# SHEET1.net
KiCad netlist of a schematic drawn in Altium Designer
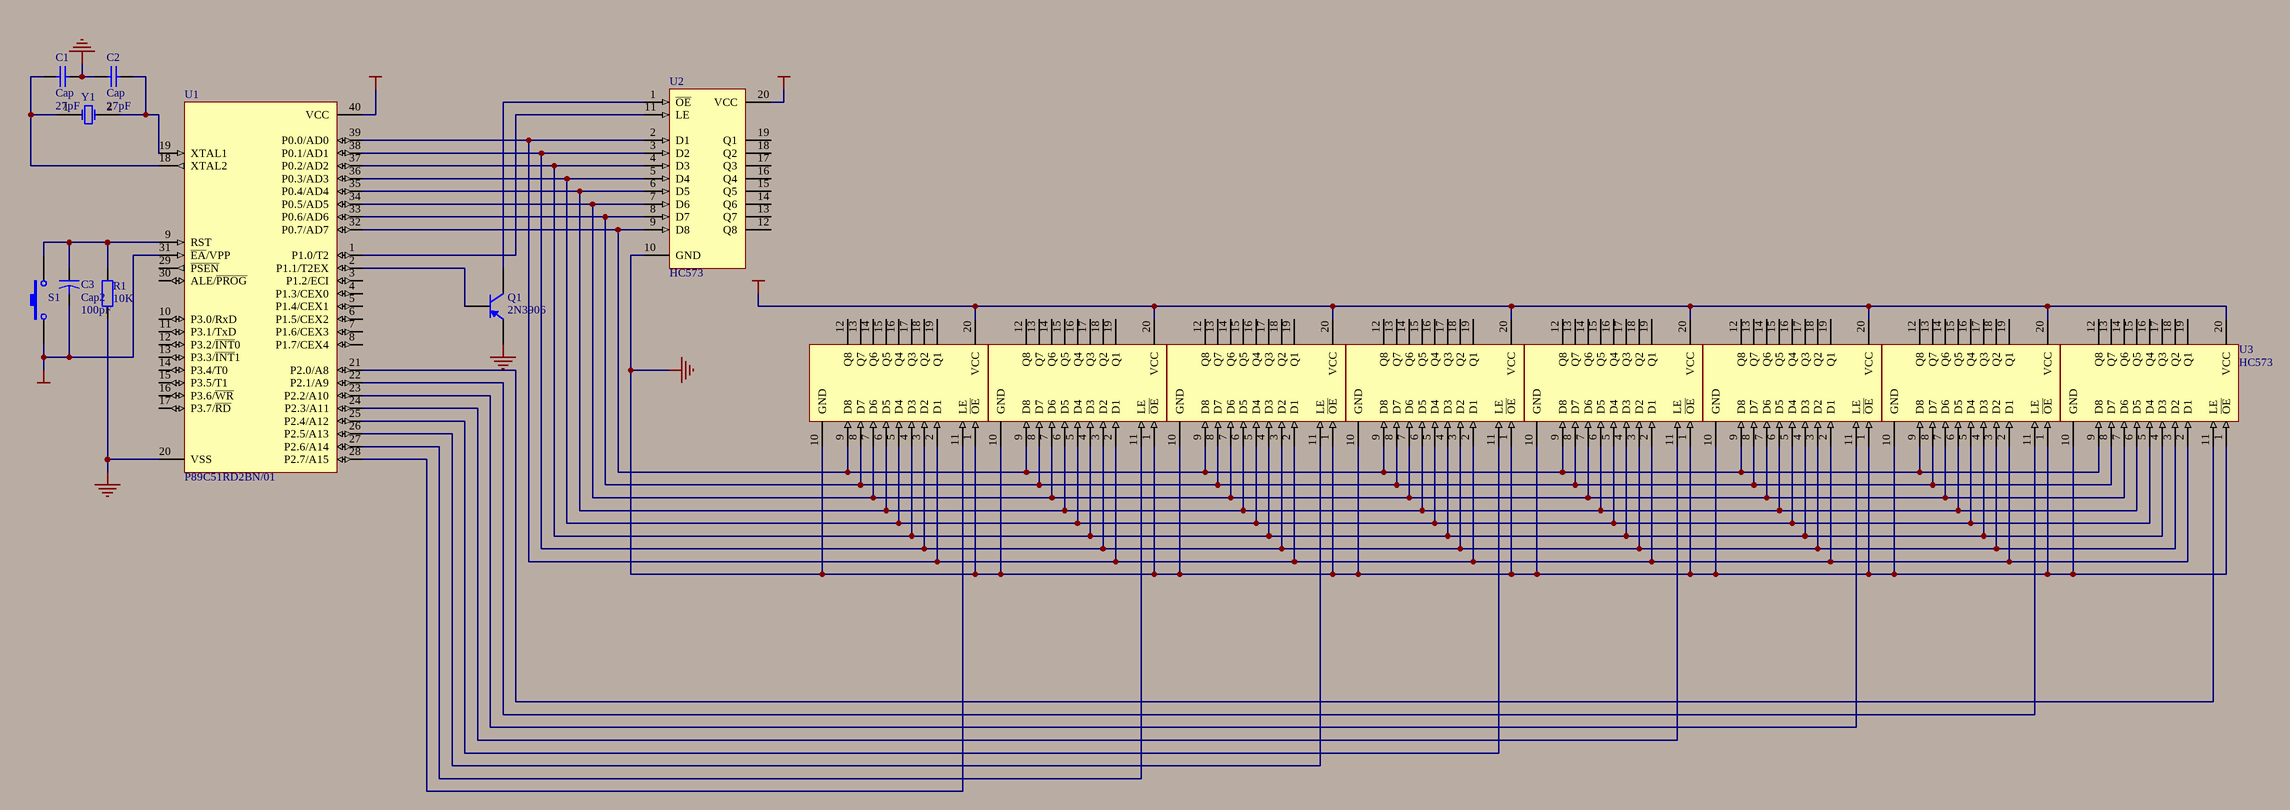
[diagram p0: SHEET1.SCHDOC]

(export (version "E")
  (design (tool "Eeschema 10.0.6"))
  (components
    (comp (ref "7")
      (value "HC573")
      (footprint "CDIP20")
      (description "Octal D-Type Latch with 3-State Output Non-Inverting")
      (fields (field (name "PUBLISHER") "Altium Limited"))
      (libsource (lib "ST Logic Latch") (part "M54HC573F1R"))
    )
    (comp (ref "C1")
      (value "Cap")
      (footprint "RAD-0.3")
      (description "Capacitor")
      (fields (field (name "ALTIUM_VALUE") "27pF") (field (name "PUBLISHER") "Altium Limited"))
      (libsource (lib "Miscellaneous Devices") (part "Cap"))
    )
    (comp (ref "C2")
      (value "Cap")
      (footprint "RAD-0.3")
      (description "Capacitor")
      (fields (field (name "ALTIUM_VALUE") "27pF") (field (name "PUBLISHER") "Altium Limited"))
      (libsource (lib "Miscellaneous Devices") (part "Cap"))
    )
    (comp (ref "C3")
      (value "Cap2")
      (footprint "CAPR5-4X5")
      (description "Capacitor")
      (fields (field (name "ALTIUM_VALUE") "100pF") (field (name "PUBLISHER") "Altium Limited"))
      (libsource (lib "Miscellaneous Devices") (part "Cap2"))
    )
    (comp (ref "Q1")
      (value "2N3906")
      (footprint "BCY-W3/E4")
      (description "PNP General Purpose Amplifier")
      (fields (field (name "PUBLISHER") "Altium Limited"))
      (libsource (lib "Miscellaneous Devices") (part "2N3906"))
    )
    (comp (ref "R1")
      (value "10K")
      (footprint "AXIAL-0.4")
      (description "Resistor")
      (fields (field (name "Comment") "Res2") (field (name "PUBLISHER") "Altium Limited"))
      (libsource (lib "Miscellaneous Devices") (part "Res2"))
    )
    (comp (ref "S1")
      (value "SW-PB")
      (footprint "SPST-2")
      (description "Switch")
      (fields (field (name "PUBLISHER") "Altium Limited"))
      (libsource (lib "Miscellaneous Devices") (part "SW-PB"))
    )
    (comp (ref "U1")
      (value "P89C51RD2BN/01")
      (footprint "SOT129-1")
      (description "80C51 8-Bit Flash Microcontroller Family, 64 kB ISP/IAP Flash with 1 kB RAM.")
      (fields (field (name "PUBLISHER") "Altium Limited"))
      (libsource (lib "Philips Microcontroller 8-Bit") (part "P89C51RD2BN/01"))
    )
    (comp (ref "U2")
      (value "HC573")
      (footprint "CDIP20")
      (description "Octal D-Type Latch with 3-State Output Non-Inverting")
      (fields (field (name "PUBLISHER") "Altium Limited"))
      (libsource (lib "ST Logic Latch") (part "M54HC573F1R"))
    )
    (comp (ref "U3")
      (value "HC573")
      (footprint "CDIP20")
      (description "Octal D-Type Latch with 3-State Output Non-Inverting")
      (fields (field (name "PUBLISHER") "Altium Limited"))
      (libsource (lib "ST Logic Latch") (part "M54HC573F1R"))
    )
    (comp (ref "U4")
      (value "HC573")
      (footprint "CDIP20")
      (description "Octal D-Type Latch with 3-State Output Non-Inverting")
      (fields (field (name "PUBLISHER") "Altium Limited"))
      (libsource (lib "ST Logic Latch") (part "M54HC573F1R"))
    )
    (comp (ref "U5")
      (value "HC573")
      (footprint "CDIP20")
      (description "Octal D-Type Latch with 3-State Output Non-Inverting")
      (fields (field (name "PUBLISHER") "Altium Limited"))
      (libsource (lib "ST Logic Latch") (part "M54HC573F1R"))
    )
    (comp (ref "U6")
      (value "HC573")
      (footprint "CDIP20")
      (description "Octal D-Type Latch with 3-State Output Non-Inverting")
      (fields (field (name "PUBLISHER") "Altium Limited"))
      (libsource (lib "ST Logic Latch") (part "M54HC573F1R"))
    )
    (comp (ref "U8")
      (value "HC573")
      (footprint "CDIP20")
      (description "Octal D-Type Latch with 3-State Output Non-Inverting")
      (fields (field (name "PUBLISHER") "Altium Limited"))
      (libsource (lib "ST Logic Latch") (part "M54HC573F1R"))
    )
    (comp (ref "U9")
      (value "HC573")
      (footprint "CDIP20")
      (description "Octal D-Type Latch with 3-State Output Non-Inverting")
      (fields (field (name "PUBLISHER") "Altium Limited"))
      (libsource (lib "ST Logic Latch") (part "M54HC573F1R"))
    )
    (comp (ref "U10")
      (value "HC573")
      (footprint "CDIP20")
      (description "Octal D-Type Latch with 3-State Output Non-Inverting")
      (fields (field (name "PUBLISHER") "Altium Limited"))
      (libsource (lib "ST Logic Latch") (part "M54HC573F1R"))
    )
    (comp (ref "Y1")
      (value "XTAL")
      (footprint "BCY-W2/D3.1")
      (description "Crystal Oscillator")
      (fields (field (name "PUBLISHER") "Altium Limited"))
      (libsource (lib "Miscellaneous Devices") (part "XTAL"))
    )
  )
  (nets
    (net (code "1") (name "GND") (class "Default")
      (node (ref "7") (pin "1") (pinfunction "~{OE}_1") (pintype "input"))
      (node (ref "7") (pin "10") (pinfunction "GND_10") (pintype "power_in"))
      (node (ref "C1") (pin "2") (pinfunction "2_2") (pintype "passive"))
      (node (ref "C2") (pin "1") (pinfunction "1_1") (pintype "passive"))
      (node (ref "Q1") (pin "1") (pinfunction "E_1") (pintype "passive"))
      (node (ref "R1") (pin "1") (pinfunction "1_1") (pintype "passive"))
      (node (ref "U1") (pin "20") (pinfunction "VSS_20") (pintype "power_in"))
      (node (ref "U10") (pin "1") (pinfunction "~{OE}_1") (pintype "input"))
      (node (ref "U10") (pin "10") (pinfunction "GND_10") (pintype "power_in"))
      (node (ref "U2") (pin "10") (pinfunction "GND_10") (pintype "power_in"))
      (node (ref "U3") (pin "1") (pinfunction "~{OE}_1") (pintype "input"))
      (node (ref "U3") (pin "10") (pinfunction "GND_10") (pintype "power_in"))
      (node (ref "U4") (pin "1") (pinfunction "~{OE}_1") (pintype "input"))
      (node (ref "U4") (pin "10") (pinfunction "GND_10") (pintype "power_in"))
      (node (ref "U5") (pin "1") (pinfunction "~{OE}_1") (pintype "input"))
      (node (ref "U5") (pin "10") (pinfunction "GND_10") (pintype "power_in"))
      (node (ref "U6") (pin "1") (pinfunction "~{OE}_1") (pintype "input"))
      (node (ref "U6") (pin "10") (pinfunction "GND_10") (pintype "power_in"))
      (node (ref "U8") (pin "1") (pinfunction "~{OE}_1") (pintype "input"))
      (node (ref "U8") (pin "10") (pinfunction "GND_10") (pintype "power_in"))
      (node (ref "U9") (pin "1") (pinfunction "~{OE}_1") (pintype "input"))
      (node (ref "U9") (pin "10") (pinfunction "GND_10") (pintype "power_in"))
    )
    (net (code "2") (name "Net-(7-D1)") (class "Default")
      (node (ref "7") (pin "2") (pinfunction "D1_2") (pintype "input"))
      (node (ref "U1") (pin "39") (pinfunction "P0.0/AD0_39") (pintype "bidirectional"))
      (node (ref "U10") (pin "2") (pinfunction "D1_2") (pintype "input"))
      (node (ref "U2") (pin "2") (pinfunction "D1_2") (pintype "input"))
      (node (ref "U3") (pin "2") (pinfunction "D1_2") (pintype "input"))
      (node (ref "U4") (pin "2") (pinfunction "D1_2") (pintype "input"))
      (node (ref "U5") (pin "2") (pinfunction "D1_2") (pintype "input"))
      (node (ref "U6") (pin "2") (pinfunction "D1_2") (pintype "input"))
      (node (ref "U8") (pin "2") (pinfunction "D1_2") (pintype "input"))
      (node (ref "U9") (pin "2") (pinfunction "D1_2") (pintype "input"))
    )
    (net (code "3") (name "Net-(7-D2)") (class "Default")
      (node (ref "7") (pin "3") (pinfunction "D2_3") (pintype "input"))
      (node (ref "U1") (pin "38") (pinfunction "P0.1/AD1_38") (pintype "bidirectional"))
      (node (ref "U10") (pin "3") (pinfunction "D2_3") (pintype "input"))
      (node (ref "U2") (pin "3") (pinfunction "D2_3") (pintype "input"))
      (node (ref "U3") (pin "3") (pinfunction "D2_3") (pintype "input"))
      (node (ref "U4") (pin "3") (pinfunction "D2_3") (pintype "input"))
      (node (ref "U5") (pin "3") (pinfunction "D2_3") (pintype "input"))
      (node (ref "U6") (pin "3") (pinfunction "D2_3") (pintype "input"))
      (node (ref "U8") (pin "3") (pinfunction "D2_3") (pintype "input"))
      (node (ref "U9") (pin "3") (pinfunction "D2_3") (pintype "input"))
    )
    (net (code "4") (name "Net-(7-D3)") (class "Default")
      (node (ref "7") (pin "4") (pinfunction "D3_4") (pintype "input"))
      (node (ref "U1") (pin "37") (pinfunction "P0.2/AD2_37") (pintype "bidirectional"))
      (node (ref "U10") (pin "4") (pinfunction "D3_4") (pintype "input"))
      (node (ref "U2") (pin "4") (pinfunction "D3_4") (pintype "input"))
      (node (ref "U3") (pin "4") (pinfunction "D3_4") (pintype "input"))
      (node (ref "U4") (pin "4") (pinfunction "D3_4") (pintype "input"))
      (node (ref "U5") (pin "4") (pinfunction "D3_4") (pintype "input"))
      (node (ref "U6") (pin "4") (pinfunction "D3_4") (pintype "input"))
      (node (ref "U8") (pin "4") (pinfunction "D3_4") (pintype "input"))
      (node (ref "U9") (pin "4") (pinfunction "D3_4") (pintype "input"))
    )
    (net (code "5") (name "Net-(7-D4)") (class "Default")
      (node (ref "7") (pin "5") (pinfunction "D4_5") (pintype "input"))
      (node (ref "U1") (pin "36") (pinfunction "P0.3/AD3_36") (pintype "bidirectional"))
      (node (ref "U10") (pin "5") (pinfunction "D4_5") (pintype "input"))
      (node (ref "U2") (pin "5") (pinfunction "D4_5") (pintype "input"))
      (node (ref "U3") (pin "5") (pinfunction "D4_5") (pintype "input"))
      (node (ref "U4") (pin "5") (pinfunction "D4_5") (pintype "input"))
      (node (ref "U5") (pin "5") (pinfunction "D4_5") (pintype "input"))
      (node (ref "U6") (pin "5") (pinfunction "D4_5") (pintype "input"))
      (node (ref "U8") (pin "5") (pinfunction "D4_5") (pintype "input"))
      (node (ref "U9") (pin "5") (pinfunction "D4_5") (pintype "input"))
    )
    (net (code "6") (name "Net-(7-D5)") (class "Default")
      (node (ref "7") (pin "6") (pinfunction "D5_6") (pintype "input"))
      (node (ref "U1") (pin "35") (pinfunction "P0.4/AD4_35") (pintype "bidirectional"))
      (node (ref "U10") (pin "6") (pinfunction "D5_6") (pintype "input"))
      (node (ref "U2") (pin "6") (pinfunction "D5_6") (pintype "input"))
      (node (ref "U3") (pin "6") (pinfunction "D5_6") (pintype "input"))
      (node (ref "U4") (pin "6") (pinfunction "D5_6") (pintype "input"))
      (node (ref "U5") (pin "6") (pinfunction "D5_6") (pintype "input"))
      (node (ref "U6") (pin "6") (pinfunction "D5_6") (pintype "input"))
      (node (ref "U8") (pin "6") (pinfunction "D5_6") (pintype "input"))
      (node (ref "U9") (pin "6") (pinfunction "D5_6") (pintype "input"))
    )
    (net (code "7") (name "Net-(7-D6)") (class "Default")
      (node (ref "7") (pin "7") (pinfunction "D6_7") (pintype "input"))
      (node (ref "U1") (pin "34") (pinfunction "P0.5/AD5_34") (pintype "bidirectional"))
      (node (ref "U10") (pin "7") (pinfunction "D6_7") (pintype "input"))
      (node (ref "U2") (pin "7") (pinfunction "D6_7") (pintype "input"))
      (node (ref "U3") (pin "7") (pinfunction "D6_7") (pintype "input"))
      (node (ref "U4") (pin "7") (pinfunction "D6_7") (pintype "input"))
      (node (ref "U5") (pin "7") (pinfunction "D6_7") (pintype "input"))
      (node (ref "U6") (pin "7") (pinfunction "D6_7") (pintype "input"))
      (node (ref "U8") (pin "7") (pinfunction "D6_7") (pintype "input"))
      (node (ref "U9") (pin "7") (pinfunction "D6_7") (pintype "input"))
    )
    (net (code "8") (name "Net-(7-D7)") (class "Default")
      (node (ref "7") (pin "8") (pinfunction "D7_8") (pintype "input"))
      (node (ref "U1") (pin "33") (pinfunction "P0.6/AD6_33") (pintype "bidirectional"))
      (node (ref "U10") (pin "8") (pinfunction "D7_8") (pintype "input"))
      (node (ref "U2") (pin "8") (pinfunction "D7_8") (pintype "input"))
      (node (ref "U3") (pin "8") (pinfunction "D7_8") (pintype "input"))
      (node (ref "U4") (pin "8") (pinfunction "D7_8") (pintype "input"))
      (node (ref "U5") (pin "8") (pinfunction "D7_8") (pintype "input"))
      (node (ref "U6") (pin "8") (pinfunction "D7_8") (pintype "input"))
      (node (ref "U8") (pin "8") (pinfunction "D7_8") (pintype "input"))
      (node (ref "U9") (pin "8") (pinfunction "D7_8") (pintype "input"))
    )
    (net (code "9") (name "Net-(7-D8)") (class "Default")
      (node (ref "7") (pin "9") (pinfunction "D8_9") (pintype "input"))
      (node (ref "U1") (pin "32") (pinfunction "P0.7/AD7_32") (pintype "bidirectional"))
      (node (ref "U10") (pin "9") (pinfunction "D8_9") (pintype "input"))
      (node (ref "U2") (pin "9") (pinfunction "D8_9") (pintype "input"))
      (node (ref "U3") (pin "9") (pinfunction "D8_9") (pintype "input"))
      (node (ref "U4") (pin "9") (pinfunction "D8_9") (pintype "input"))
      (node (ref "U5") (pin "9") (pinfunction "D8_9") (pintype "input"))
      (node (ref "U6") (pin "9") (pinfunction "D8_9") (pintype "input"))
      (node (ref "U8") (pin "9") (pinfunction "D8_9") (pintype "input"))
      (node (ref "U9") (pin "9") (pinfunction "D8_9") (pintype "input"))
    )
    (net (code "10") (name "Net-(7-LE)") (class "Default")
      (node (ref "7") (pin "11") (pinfunction "LE_11") (pintype "input"))
      (node (ref "U1") (pin "25") (pinfunction "P2.4/A12_25") (pintype "bidirectional"))
    )
    (net (code "11") (name "Net-(Q1-B)") (class "Default")
      (node (ref "Q1") (pin "2") (pinfunction "B_2") (pintype "passive"))
      (node (ref "U1") (pin "2") (pinfunction "P1.1/T2EX_2") (pintype "bidirectional"))
    )
    (net (code "12") (name "Net-(Q1-C)") (class "Default")
      (node (ref "Q1") (pin "3") (pinfunction "C_3") (pintype "passive"))
      (node (ref "U2") (pin "1") (pinfunction "~{OE}_1") (pintype "input"))
    )
    (net (code "13") (name "Net-(U1-P1.0{slash}T2)") (class "Default")
      (node (ref "U1") (pin "1") (pinfunction "P1.0/T2_1") (pintype "bidirectional"))
      (node (ref "U2") (pin "11") (pinfunction "LE_11") (pintype "input"))
    )
    (net (code "14") (name "Net-(U1-P2.0{slash}A8)") (class "Default")
      (node (ref "U1") (pin "21") (pinfunction "P2.0/A8_21") (pintype "bidirectional"))
      (node (ref "U3") (pin "11") (pinfunction "LE_11") (pintype "input"))
    )
    (net (code "15") (name "Net-(U1-P2.1{slash}A9)") (class "Default")
      (node (ref "U1") (pin "22") (pinfunction "P2.1/A9_22") (pintype "bidirectional"))
      (node (ref "U4") (pin "11") (pinfunction "LE_11") (pintype "input"))
    )
    (net (code "16") (name "Net-(U1-P2.2{slash}A10)") (class "Default")
      (node (ref "U1") (pin "23") (pinfunction "P2.2/A10_23") (pintype "bidirectional"))
      (node (ref "U5") (pin "11") (pinfunction "LE_11") (pintype "input"))
    )
    (net (code "17") (name "Net-(U1-P2.3{slash}A11)") (class "Default")
      (node (ref "U1") (pin "24") (pinfunction "P2.3/A11_24") (pintype "bidirectional"))
      (node (ref "U6") (pin "11") (pinfunction "LE_11") (pintype "input"))
    )
    (net (code "18") (name "Net-(U1-P2.5{slash}A13)") (class "Default")
      (node (ref "U1") (pin "26") (pinfunction "P2.5/A13_26") (pintype "bidirectional"))
      (node (ref "U8") (pin "11") (pinfunction "LE_11") (pintype "input"))
    )
    (net (code "19") (name "Net-(U1-P2.6{slash}A14)") (class "Default")
      (node (ref "U1") (pin "27") (pinfunction "P2.6/A14_27") (pintype "bidirectional"))
      (node (ref "U9") (pin "11") (pinfunction "LE_11") (pintype "input"))
    )
    (net (code "20") (name "Net-(U1-P2.7{slash}A15)") (class "Default")
      (node (ref "U1") (pin "28") (pinfunction "P2.7/A15_28") (pintype "bidirectional"))
      (node (ref "U10") (pin "11") (pinfunction "LE_11") (pintype "input"))
    )
    (net (code "21") (name "Net-(U1-RST)") (class "Default")
      (node (ref "C3") (pin "1") (pinfunction "1_1") (pintype "passive"))
      (node (ref "R1") (pin "2") (pinfunction "2_2") (pintype "passive"))
      (node (ref "S1") (pin "2") (pinfunction "2_2") (pintype "passive"))
      (node (ref "U1") (pin "9") (pinfunction "RST_9") (pintype "input"))
    )
    (net (code "22") (name "Net-(U1-XTAL1)") (class "Default")
      (node (ref "C2") (pin "2") (pinfunction "2_2") (pintype "passive"))
      (node (ref "U1") (pin "19") (pinfunction "XTAL1_19") (pintype "input"))
      (node (ref "Y1") (pin "2") (pinfunction "OSC2_2") (pintype "passive"))
    )
    (net (code "23") (name "Net-(U1-XTAL2)") (class "Default")
      (node (ref "C1") (pin "1") (pinfunction "1_1") (pintype "passive"))
      (node (ref "U1") (pin "18") (pinfunction "XTAL2_18") (pintype "output"))
      (node (ref "Y1") (pin "1") (pinfunction "OSC1_1") (pintype "passive"))
    )
    (net (code "24") (name "VCC") (class "Default")
      (node (ref "7") (pin "20") (pinfunction "VCC_20") (pintype "power_in"))
      (node (ref "C3") (pin "2") (pinfunction "2_2") (pintype "passive"))
      (node (ref "S1") (pin "1") (pinfunction "1_1") (pintype "passive"))
      (node (ref "U1") (pin "31") (pinfunction "~{EA}/VPP_31") (pintype "input"))
      (node (ref "U1") (pin "40") (pinfunction "VCC_40") (pintype "power_in"))
      (node (ref "U10") (pin "20") (pinfunction "VCC_20") (pintype "power_in"))
      (node (ref "U2") (pin "20") (pinfunction "VCC_20") (pintype "power_in"))
      (node (ref "U3") (pin "20") (pinfunction "VCC_20") (pintype "power_in"))
      (node (ref "U4") (pin "20") (pinfunction "VCC_20") (pintype "power_in"))
      (node (ref "U5") (pin "20") (pinfunction "VCC_20") (pintype "power_in"))
      (node (ref "U6") (pin "20") (pinfunction "VCC_20") (pintype "power_in"))
      (node (ref "U8") (pin "20") (pinfunction "VCC_20") (pintype "power_in"))
      (node (ref "U9") (pin "20") (pinfunction "VCC_20") (pintype "power_in"))
    )
    (net (code "25") (name "unconnected-(7-Q1-Pad19)") (class "Default")
      (node (ref "7") (pin "19") (pinfunction "Q1_19") (pintype "tri_state"))
    )
    (net (code "26") (name "unconnected-(7-Q2-Pad18)") (class "Default")
      (node (ref "7") (pin "18") (pinfunction "Q2_18") (pintype "tri_state"))
    )
    (net (code "27") (name "unconnected-(7-Q3-Pad17)") (class "Default")
      (node (ref "7") (pin "17") (pinfunction "Q3_17") (pintype "tri_state"))
    )
    (net (code "28") (name "unconnected-(7-Q4-Pad16)") (class "Default")
      (node (ref "7") (pin "16") (pinfunction "Q4_16") (pintype "tri_state"))
    )
    (net (code "29") (name "unconnected-(7-Q5-Pad15)") (class "Default")
      (node (ref "7") (pin "15") (pinfunction "Q5_15") (pintype "tri_state"))
    )
    (net (code "30") (name "unconnected-(7-Q6-Pad14)") (class "Default")
      (node (ref "7") (pin "14") (pinfunction "Q6_14") (pintype "tri_state"))
    )
    (net (code "31") (name "unconnected-(7-Q7-Pad13)") (class "Default")
      (node (ref "7") (pin "13") (pinfunction "Q7_13") (pintype "tri_state"))
    )
    (net (code "32") (name "unconnected-(7-Q8-Pad12)") (class "Default")
      (node (ref "7") (pin "12") (pinfunction "Q8_12") (pintype "tri_state"))
    )
    (net (code "33") (name "unconnected-(U1-ALE{slash}~{PROG}-Pad30)") (class "Default")
      (node (ref "U1") (pin "30") (pinfunction "ALE/~{PROG}_30") (pintype "bidirectional"))
    )
    (net (code "34") (name "unconnected-(U1-P1.2{slash}ECI-Pad3)") (class "Default")
      (node (ref "U1") (pin "3") (pinfunction "P1.2/ECI_3") (pintype "bidirectional"))
    )
    (net (code "35") (name "unconnected-(U1-P1.3{slash}CEX0-Pad4)") (class "Default")
      (node (ref "U1") (pin "4") (pinfunction "P1.3/CEX0_4") (pintype "bidirectional"))
    )
    (net (code "36") (name "unconnected-(U1-P1.4{slash}CEX1-Pad5)") (class "Default")
      (node (ref "U1") (pin "5") (pinfunction "P1.4/CEX1_5") (pintype "bidirectional"))
    )
    (net (code "37") (name "unconnected-(U1-P1.5{slash}CEX2-Pad6)") (class "Default")
      (node (ref "U1") (pin "6") (pinfunction "P1.5/CEX2_6") (pintype "bidirectional"))
    )
    (net (code "38") (name "unconnected-(U1-P1.6{slash}CEX3-Pad7)") (class "Default")
      (node (ref "U1") (pin "7") (pinfunction "P1.6/CEX3_7") (pintype "bidirectional"))
    )
    (net (code "39") (name "unconnected-(U1-P1.7{slash}CEX4-Pad8)") (class "Default")
      (node (ref "U1") (pin "8") (pinfunction "P1.7/CEX4_8") (pintype "bidirectional"))
    )
    (net (code "40") (name "unconnected-(U1-P3.0{slash}RxD-Pad10)") (class "Default")
      (node (ref "U1") (pin "10") (pinfunction "P3.0/RxD_10") (pintype "bidirectional"))
    )
    (net (code "41") (name "unconnected-(U1-P3.1{slash}TxD-Pad11)") (class "Default")
      (node (ref "U1") (pin "11") (pinfunction "P3.1/TxD_11") (pintype "bidirectional"))
    )
    (net (code "42") (name "unconnected-(U1-P3.2{slash}~{INT}0-Pad12)") (class "Default")
      (node (ref "U1") (pin "12") (pinfunction "P3.2/~{INT}0_12") (pintype "bidirectional"))
    )
    (net (code "43") (name "unconnected-(U1-P3.3{slash}~{INT}1-Pad13)") (class "Default")
      (node (ref "U1") (pin "13") (pinfunction "P3.3/~{INT}1_13") (pintype "bidirectional"))
    )
    (net (code "44") (name "unconnected-(U1-P3.4{slash}T0-Pad14)") (class "Default")
      (node (ref "U1") (pin "14") (pinfunction "P3.4/T0_14") (pintype "bidirectional"))
    )
    (net (code "45") (name "unconnected-(U1-P3.5{slash}T1-Pad15)") (class "Default")
      (node (ref "U1") (pin "15") (pinfunction "P3.5/T1_15") (pintype "bidirectional"))
    )
    (net (code "46") (name "unconnected-(U1-P3.6{slash}~{WR}-Pad16)") (class "Default")
      (node (ref "U1") (pin "16") (pinfunction "P3.6/~{WR}_16") (pintype "bidirectional"))
    )
    (net (code "47") (name "unconnected-(U1-P3.7{slash}~{RD}-Pad17)") (class "Default")
      (node (ref "U1") (pin "17") (pinfunction "P3.7/~{RD}_17") (pintype "bidirectional"))
    )
    (net (code "48") (name "unconnected-(U1-~{PSEN}-Pad29)") (class "Default")
      (node (ref "U1") (pin "29") (pinfunction "~{PSEN}_29") (pintype "output"))
    )
    (net (code "49") (name "unconnected-(U2-Q1-Pad19)") (class "Default")
      (node (ref "U2") (pin "19") (pinfunction "Q1_19") (pintype "tri_state"))
    )
    (net (code "50") (name "unconnected-(U2-Q2-Pad18)") (class "Default")
      (node (ref "U2") (pin "18") (pinfunction "Q2_18") (pintype "tri_state"))
    )
    (net (code "51") (name "unconnected-(U2-Q3-Pad17)") (class "Default")
      (node (ref "U2") (pin "17") (pinfunction "Q3_17") (pintype "tri_state"))
    )
    (net (code "52") (name "unconnected-(U2-Q4-Pad16)") (class "Default")
      (node (ref "U2") (pin "16") (pinfunction "Q4_16") (pintype "tri_state"))
    )
    (net (code "53") (name "unconnected-(U2-Q5-Pad15)") (class "Default")
      (node (ref "U2") (pin "15") (pinfunction "Q5_15") (pintype "tri_state"))
    )
    (net (code "54") (name "unconnected-(U2-Q6-Pad14)") (class "Default")
      (node (ref "U2") (pin "14") (pinfunction "Q6_14") (pintype "tri_state"))
    )
    (net (code "55") (name "unconnected-(U2-Q7-Pad13)") (class "Default")
      (node (ref "U2") (pin "13") (pinfunction "Q7_13") (pintype "tri_state"))
    )
    (net (code "56") (name "unconnected-(U2-Q8-Pad12)") (class "Default")
      (node (ref "U2") (pin "12") (pinfunction "Q8_12") (pintype "tri_state"))
    )
    (net (code "57") (name "unconnected-(U3-Q1-Pad19)") (class "Default")
      (node (ref "U3") (pin "19") (pinfunction "Q1_19") (pintype "tri_state"))
    )
    (net (code "58") (name "unconnected-(U3-Q2-Pad18)") (class "Default")
      (node (ref "U3") (pin "18") (pinfunction "Q2_18") (pintype "tri_state"))
    )
    (net (code "59") (name "unconnected-(U3-Q3-Pad17)") (class "Default")
      (node (ref "U3") (pin "17") (pinfunction "Q3_17") (pintype "tri_state"))
    )
    (net (code "60") (name "unconnected-(U3-Q4-Pad16)") (class "Default")
      (node (ref "U3") (pin "16") (pinfunction "Q4_16") (pintype "tri_state"))
    )
    (net (code "61") (name "unconnected-(U3-Q5-Pad15)") (class "Default")
      (node (ref "U3") (pin "15") (pinfunction "Q5_15") (pintype "tri_state"))
    )
    (net (code "62") (name "unconnected-(U3-Q6-Pad14)") (class "Default")
      (node (ref "U3") (pin "14") (pinfunction "Q6_14") (pintype "tri_state"))
    )
    (net (code "63") (name "unconnected-(U3-Q7-Pad13)") (class "Default")
      (node (ref "U3") (pin "13") (pinfunction "Q7_13") (pintype "tri_state"))
    )
    (net (code "64") (name "unconnected-(U3-Q8-Pad12)") (class "Default")
      (node (ref "U3") (pin "12") (pinfunction "Q8_12") (pintype "tri_state"))
    )
    (net (code "65") (name "unconnected-(U4-Q1-Pad19)") (class "Default")
      (node (ref "U4") (pin "19") (pinfunction "Q1_19") (pintype "tri_state"))
    )
    (net (code "66") (name "unconnected-(U4-Q2-Pad18)") (class "Default")
      (node (ref "U4") (pin "18") (pinfunction "Q2_18") (pintype "tri_state"))
    )
    (net (code "67") (name "unconnected-(U4-Q3-Pad17)") (class "Default")
      (node (ref "U4") (pin "17") (pinfunction "Q3_17") (pintype "tri_state"))
    )
    (net (code "68") (name "unconnected-(U4-Q4-Pad16)") (class "Default")
      (node (ref "U4") (pin "16") (pinfunction "Q4_16") (pintype "tri_state"))
    )
    (net (code "69") (name "unconnected-(U4-Q5-Pad15)") (class "Default")
      (node (ref "U4") (pin "15") (pinfunction "Q5_15") (pintype "tri_state"))
    )
    (net (code "70") (name "unconnected-(U4-Q6-Pad14)") (class "Default")
      (node (ref "U4") (pin "14") (pinfunction "Q6_14") (pintype "tri_state"))
    )
    (net (code "71") (name "unconnected-(U4-Q7-Pad13)") (class "Default")
      (node (ref "U4") (pin "13") (pinfunction "Q7_13") (pintype "tri_state"))
    )
    (net (code "72") (name "unconnected-(U4-Q8-Pad12)") (class "Default")
      (node (ref "U4") (pin "12") (pinfunction "Q8_12") (pintype "tri_state"))
    )
    (net (code "73") (name "unconnected-(U5-Q1-Pad19)") (class "Default")
      (node (ref "U5") (pin "19") (pinfunction "Q1_19") (pintype "tri_state"))
    )
    (net (code "74") (name "unconnected-(U5-Q2-Pad18)") (class "Default")
      (node (ref "U5") (pin "18") (pinfunction "Q2_18") (pintype "tri_state"))
    )
    (net (code "75") (name "unconnected-(U5-Q3-Pad17)") (class "Default")
      (node (ref "U5") (pin "17") (pinfunction "Q3_17") (pintype "tri_state"))
    )
    (net (code "76") (name "unconnected-(U5-Q4-Pad16)") (class "Default")
      (node (ref "U5") (pin "16") (pinfunction "Q4_16") (pintype "tri_state"))
    )
    (net (code "77") (name "unconnected-(U5-Q5-Pad15)") (class "Default")
      (node (ref "U5") (pin "15") (pinfunction "Q5_15") (pintype "tri_state"))
    )
    (net (code "78") (name "unconnected-(U5-Q6-Pad14)") (class "Default")
      (node (ref "U5") (pin "14") (pinfunction "Q6_14") (pintype "tri_state"))
    )
    (net (code "79") (name "unconnected-(U5-Q7-Pad13)") (class "Default")
      (node (ref "U5") (pin "13") (pinfunction "Q7_13") (pintype "tri_state"))
    )
    (net (code "80") (name "unconnected-(U5-Q8-Pad12)") (class "Default")
      (node (ref "U5") (pin "12") (pinfunction "Q8_12") (pintype "tri_state"))
    )
    (net (code "81") (name "unconnected-(U6-Q1-Pad19)") (class "Default")
      (node (ref "U6") (pin "19") (pinfunction "Q1_19") (pintype "tri_state"))
    )
    (net (code "82") (name "unconnected-(U6-Q2-Pad18)") (class "Default")
      (node (ref "U6") (pin "18") (pinfunction "Q2_18") (pintype "tri_state"))
    )
    (net (code "83") (name "unconnected-(U6-Q3-Pad17)") (class "Default")
      (node (ref "U6") (pin "17") (pinfunction "Q3_17") (pintype "tri_state"))
    )
    (net (code "84") (name "unconnected-(U6-Q4-Pad16)") (class "Default")
      (node (ref "U6") (pin "16") (pinfunction "Q4_16") (pintype "tri_state"))
    )
    (net (code "85") (name "unconnected-(U6-Q5-Pad15)") (class "Default")
      (node (ref "U6") (pin "15") (pinfunction "Q5_15") (pintype "tri_state"))
    )
    (net (code "86") (name "unconnected-(U6-Q6-Pad14)") (class "Default")
      (node (ref "U6") (pin "14") (pinfunction "Q6_14") (pintype "tri_state"))
    )
    (net (code "87") (name "unconnected-(U6-Q7-Pad13)") (class "Default")
      (node (ref "U6") (pin "13") (pinfunction "Q7_13") (pintype "tri_state"))
    )
    (net (code "88") (name "unconnected-(U6-Q8-Pad12)") (class "Default")
      (node (ref "U6") (pin "12") (pinfunction "Q8_12") (pintype "tri_state"))
    )
    (net (code "89") (name "unconnected-(U8-Q1-Pad19)") (class "Default")
      (node (ref "U8") (pin "19") (pinfunction "Q1_19") (pintype "tri_state"))
    )
    (net (code "90") (name "unconnected-(U8-Q2-Pad18)") (class "Default")
      (node (ref "U8") (pin "18") (pinfunction "Q2_18") (pintype "tri_state"))
    )
    (net (code "91") (name "unconnected-(U8-Q3-Pad17)") (class "Default")
      (node (ref "U8") (pin "17") (pinfunction "Q3_17") (pintype "tri_state"))
    )
    (net (code "92") (name "unconnected-(U8-Q4-Pad16)") (class "Default")
      (node (ref "U8") (pin "16") (pinfunction "Q4_16") (pintype "tri_state"))
    )
    (net (code "93") (name "unconnected-(U8-Q5-Pad15)") (class "Default")
      (node (ref "U8") (pin "15") (pinfunction "Q5_15") (pintype "tri_state"))
    )
    (net (code "94") (name "unconnected-(U8-Q6-Pad14)") (class "Default")
      (node (ref "U8") (pin "14") (pinfunction "Q6_14") (pintype "tri_state"))
    )
    (net (code "95") (name "unconnected-(U8-Q7-Pad13)") (class "Default")
      (node (ref "U8") (pin "13") (pinfunction "Q7_13") (pintype "tri_state"))
    )
    (net (code "96") (name "unconnected-(U8-Q8-Pad12)") (class "Default")
      (node (ref "U8") (pin "12") (pinfunction "Q8_12") (pintype "tri_state"))
    )
    (net (code "97") (name "unconnected-(U9-Q1-Pad19)") (class "Default")
      (node (ref "U9") (pin "19") (pinfunction "Q1_19") (pintype "tri_state"))
    )
    (net (code "98") (name "unconnected-(U9-Q2-Pad18)") (class "Default")
      (node (ref "U9") (pin "18") (pinfunction "Q2_18") (pintype "tri_state"))
    )
    (net (code "99") (name "unconnected-(U9-Q3-Pad17)") (class "Default")
      (node (ref "U9") (pin "17") (pinfunction "Q3_17") (pintype "tri_state"))
    )
    (net (code "100") (name "unconnected-(U9-Q4-Pad16)") (class "Default")
      (node (ref "U9") (pin "16") (pinfunction "Q4_16") (pintype "tri_state"))
    )
    (net (code "101") (name "unconnected-(U9-Q5-Pad15)") (class "Default")
      (node (ref "U9") (pin "15") (pinfunction "Q5_15") (pintype "tri_state"))
    )
    (net (code "102") (name "unconnected-(U9-Q6-Pad14)") (class "Default")
      (node (ref "U9") (pin "14") (pinfunction "Q6_14") (pintype "tri_state"))
    )
    (net (code "103") (name "unconnected-(U9-Q7-Pad13)") (class "Default")
      (node (ref "U9") (pin "13") (pinfunction "Q7_13") (pintype "tri_state"))
    )
    (net (code "104") (name "unconnected-(U9-Q8-Pad12)") (class "Default")
      (node (ref "U9") (pin "12") (pinfunction "Q8_12") (pintype "tri_state"))
    )
    (net (code "105") (name "unconnected-(U10-Q1-Pad19)") (class "Default")
      (node (ref "U10") (pin "19") (pinfunction "Q1_19") (pintype "tri_state"))
    )
    (net (code "106") (name "unconnected-(U10-Q2-Pad18)") (class "Default")
      (node (ref "U10") (pin "18") (pinfunction "Q2_18") (pintype "tri_state"))
    )
    (net (code "107") (name "unconnected-(U10-Q3-Pad17)") (class "Default")
      (node (ref "U10") (pin "17") (pinfunction "Q3_17") (pintype "tri_state"))
    )
    (net (code "108") (name "unconnected-(U10-Q4-Pad16)") (class "Default")
      (node (ref "U10") (pin "16") (pinfunction "Q4_16") (pintype "tri_state"))
    )
    (net (code "109") (name "unconnected-(U10-Q5-Pad15)") (class "Default")
      (node (ref "U10") (pin "15") (pinfunction "Q5_15") (pintype "tri_state"))
    )
    (net (code "110") (name "unconnected-(U10-Q6-Pad14)") (class "Default")
      (node (ref "U10") (pin "14") (pinfunction "Q6_14") (pintype "tri_state"))
    )
    (net (code "111") (name "unconnected-(U10-Q7-Pad13)") (class "Default")
      (node (ref "U10") (pin "13") (pinfunction "Q7_13") (pintype "tri_state"))
    )
    (net (code "112") (name "unconnected-(U10-Q8-Pad12)") (class "Default")
      (node (ref "U10") (pin "12") (pinfunction "Q8_12") (pintype "tri_state"))
    )
  )
)
